# Arduino.net
KiCad netlist of a schematic drawn in Altium Designer
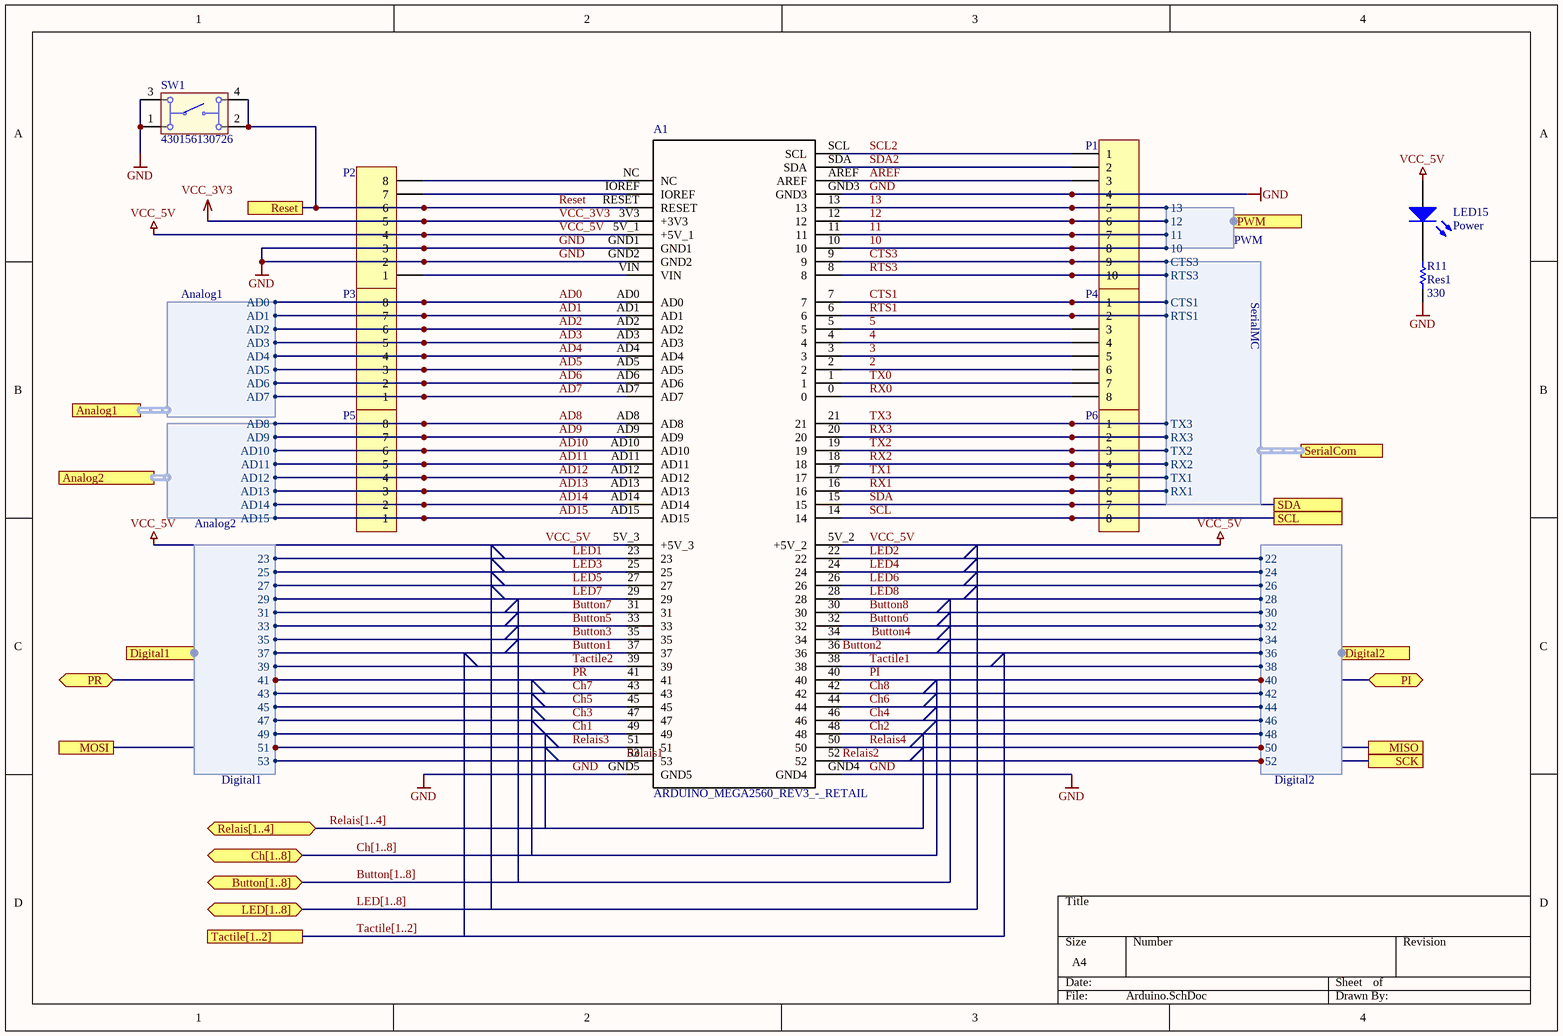
[diagram p0: Arduino.SchDoc]

(export (version "E")
  (design (tool "Eeschema 10.0.6"))
  (components
    (comp (ref "A1")
      (value "ARDUINO_MEGA2560_REV3_-_RETAIL")
      (footprint "*ARDUINO_MEGA2560_REV3_-_RETAIL_ARDUINO_MEGA2560_REV3_-_RETAIL(Primary)")
      (description "Dev.kit: Arduino; SPI, TWI, UART; ICSP, USB B, pin strips, supply")
      (fields (field (name "MF") "Arduino") (field (name "MP") "ARDUINO MEGA2560 REV3 - RETAIL"))
      (libsource (lib "ARDUINO_MEGA2560_REV3_-_RETAIL") (part "ARDUINO_MEGA2560_REV3_-_RETAIL"))
    )
    (comp (ref "LED15")
      (value "Power")
      (footprint "Type 5mm")
      (description "THT LED round mono-color waterclear, WL-TMRW, Green")
      (fields (field (name "PARTNUMBER") "151053GS03000") (field (name "MANUFACTURER") "Wuerth Elektronik"))
      (libsource (lib "Altium Content Vault") (part "WE-LED_K1A2-2"))
    )
    (comp (ref "P1")
      (value "Header 10")
      (footprint "HDR1X10")
      (description "Header, 10-Pin")
      (fields (field (name "PUBLISHER") "Altium Limited"))
      (libsource (lib "Miscellaneous Connectors") (part "Header 10"))
    )
    (comp (ref "P2")
      (value "Header 8")
      (footprint "HDR1X8")
      (description "Header, 8-Pin")
      (fields (field (name "PUBLISHER") "Altium Limited"))
      (libsource (lib "") (part "Header 8_1"))
    )
    (comp (ref "P3")
      (value "Header 8")
      (footprint "HDR1X8")
      (description "Header, 8-Pin")
      (fields (field (name "PUBLISHER") "Altium Limited"))
      (libsource (lib "") (part "Header 8_1"))
    )
    (comp (ref "P4")
      (value "Header 8")
      (footprint "HDR1X8")
      (description "Header, 8-Pin")
      (fields (field (name "PUBLISHER") "Altium Limited"))
      (libsource (lib "Miscellaneous Connectors") (part "Header 8"))
    )
    (comp (ref "P5")
      (value "Header 8")
      (footprint "HDR1X8")
      (description "Header, 8-Pin")
      (fields (field (name "PUBLISHER") "Altium Limited"))
      (libsource (lib "") (part "Header 8_1"))
    )
    (comp (ref "P6")
      (value "Header 8")
      (footprint "HDR1X8")
      (description "Header, 8-Pin")
      (fields (field (name "PUBLISHER") "Altium Limited"))
      (libsource (lib "Miscellaneous Connectors") (part "Header 8"))
    )
    (comp (ref "R11")
      (value "Res1")
      (footprint "AXIAL-0.3")
      (description "Resistor")
      (fields (field (name "ALTIUM_VALUE") "330") (field (name "PUBLISHER") "Altium Limited"))
      (libsource (lib "Miscellaneous Devices") (part "Res1"))
    )
    (comp (ref "SW1")
      (value "430156130726")
      (footprint "430156130726")
      (description "WS-TATV THT Tact Switch 6X6 mm")
      (fields (field (name "MANUFACTURER") "Wuerth Elektronik"))
      (libsource (lib "Altium Content Vault") (part "WE-TACT-SW-4"))
    )
  )
  (nets
    (net (code "7") (name "/2") (class "Default")
      (node (ref "A1") (pin "2") (pinfunction "2_2") (pintype "passive"))
      (node (ref "P4") (pin "6") (pinfunction "6_6") (pintype "passive"))
    )
    (net (code "8") (name "/3") (class "Default")
      (node (ref "A1") (pin "3") (pinfunction "3_3") (pintype "passive"))
      (node (ref "P4") (pin "5") (pinfunction "5_5") (pintype "passive"))
    )
    (net (code "9") (name "/4") (class "Default")
      (node (ref "A1") (pin "4") (pinfunction "4_4") (pintype "passive"))
      (node (ref "P4") (pin "4") (pinfunction "4_4") (pintype "passive"))
    )
    (net (code "10") (name "/5") (class "Default")
      (node (ref "A1") (pin "5") (pinfunction "5_5") (pintype "passive"))
      (node (ref "P4") (pin "3") (pinfunction "3_3") (pintype "passive"))
    )
    (net (code "11") (name "/10") (class "Default")
      (node (ref "A1") (pin "10") (pinfunction "10_10") (pintype "passive"))
      (node (ref "P1") (pin "8") (pinfunction "8_8") (pintype "passive"))
    )
    (net (code "12") (name "/11") (class "Default")
      (node (ref "A1") (pin "11") (pinfunction "11_11") (pintype "passive"))
      (node (ref "P1") (pin "7") (pinfunction "7_7") (pintype "passive"))
    )
    (net (code "13") (name "/12") (class "Default")
      (node (ref "A1") (pin "12") (pinfunction "12_12") (pintype "passive"))
      (node (ref "P1") (pin "6") (pinfunction "6_6") (pintype "passive"))
    )
    (net (code "14") (name "/13") (class "Default")
      (node (ref "A1") (pin "13") (pinfunction "13_13") (pintype "passive"))
      (node (ref "P1") (pin "5") (pinfunction "5_5") (pintype "passive"))
    )
    (net (code "15") (name "/AD0") (class "Default")
      (node (ref "A1") (pin "AD0") (pinfunction "AD0_AD0") (pintype "passive"))
      (node (ref "P3") (pin "8") (pinfunction "8_8") (pintype "passive"))
    )
    (net (code "16") (name "/AD1") (class "Default")
      (node (ref "A1") (pin "AD1") (pinfunction "AD1_AD1") (pintype "passive"))
      (node (ref "P3") (pin "7") (pinfunction "7_7") (pintype "passive"))
    )
    (net (code "17") (name "/AD2") (class "Default")
      (node (ref "A1") (pin "AD2") (pinfunction "AD2_AD2") (pintype "passive"))
      (node (ref "P3") (pin "6") (pinfunction "6_6") (pintype "passive"))
    )
    (net (code "18") (name "/AD3") (class "Default")
      (node (ref "A1") (pin "AD3") (pinfunction "AD3_AD3") (pintype "passive"))
      (node (ref "P3") (pin "5") (pinfunction "5_5") (pintype "passive"))
    )
    (net (code "19") (name "/AD4") (class "Default")
      (node (ref "A1") (pin "AD4") (pinfunction "AD4_AD4") (pintype "passive"))
      (node (ref "P3") (pin "4") (pinfunction "4_4") (pintype "passive"))
    )
    (net (code "20") (name "/AD5") (class "Default")
      (node (ref "A1") (pin "AD5") (pinfunction "AD5_AD5") (pintype "passive"))
      (node (ref "P3") (pin "3") (pinfunction "3_3") (pintype "passive"))
    )
    (net (code "21") (name "/AD6") (class "Default")
      (node (ref "A1") (pin "AD6") (pinfunction "AD6_AD6") (pintype "passive"))
      (node (ref "P3") (pin "2") (pinfunction "2_2") (pintype "passive"))
    )
    (net (code "22") (name "/AD7") (class "Default")
      (node (ref "A1") (pin "AD7") (pinfunction "AD7_AD7") (pintype "passive"))
      (node (ref "P3") (pin "1") (pinfunction "1_1") (pintype "passive"))
    )
    (net (code "23") (name "/AD8") (class "Default")
      (node (ref "A1") (pin "AD8") (pinfunction "AD8_AD8") (pintype "passive"))
      (node (ref "P5") (pin "8") (pinfunction "8_8") (pintype "passive"))
    )
    (net (code "24") (name "/AD9") (class "Default")
      (node (ref "A1") (pin "AD9") (pinfunction "AD9_AD9") (pintype "passive"))
      (node (ref "P5") (pin "7") (pinfunction "7_7") (pintype "passive"))
    )
    (net (code "25") (name "/AD10") (class "Default")
      (node (ref "A1") (pin "AD10") (pinfunction "AD10_AD10") (pintype "passive"))
      (node (ref "P5") (pin "6") (pinfunction "6_6") (pintype "passive"))
    )
    (net (code "26") (name "/AD11") (class "Default")
      (node (ref "A1") (pin "AD11") (pinfunction "AD11_AD11") (pintype "passive"))
      (node (ref "P5") (pin "5") (pinfunction "5_5") (pintype "passive"))
    )
    (net (code "27") (name "/AD12") (class "Default")
      (node (ref "A1") (pin "AD12") (pinfunction "AD12_AD12") (pintype "passive"))
      (node (ref "P5") (pin "4") (pinfunction "4_4") (pintype "passive"))
    )
    (net (code "28") (name "/AD13") (class "Default")
      (node (ref "A1") (pin "AD13") (pinfunction "AD13_AD13") (pintype "passive"))
      (node (ref "P5") (pin "3") (pinfunction "3_3") (pintype "passive"))
    )
    (net (code "29") (name "/AD14") (class "Default")
      (node (ref "A1") (pin "AD14") (pinfunction "AD14_AD14") (pintype "passive"))
      (node (ref "P5") (pin "2") (pinfunction "2_2") (pintype "passive"))
    )
    (net (code "30") (name "/AD15") (class "Default")
      (node (ref "A1") (pin "AD15") (pinfunction "AD15_AD15") (pintype "passive"))
      (node (ref "P5") (pin "1") (pinfunction "1_1") (pintype "passive"))
    )
    (net (code "31") (name "/AREF") (class "Default")
      (node (ref "A1") (pin "AREF") (pinfunction "AREF_AREF") (pintype "passive"))
      (node (ref "P1") (pin "3") (pinfunction "3_3") (pintype "passive"))
    )
    (net (code "32") (name "/Button1") (class "Default")
      (node (ref "A1") (pin "37") (pinfunction "37_37") (pintype "passive"))
    )
    (net (code "33") (name "/Button2") (class "Default")
      (node (ref "A1") (pin "36") (pinfunction "36_36") (pintype "passive"))
    )
    (net (code "34") (name "/Button3") (class "Default")
      (node (ref "A1") (pin "35") (pinfunction "35_35") (pintype "passive"))
    )
    (net (code "35") (name "/Button4") (class "Default")
      (node (ref "A1") (pin "34") (pinfunction "34_34") (pintype "passive"))
    )
    (net (code "36") (name "/Button5") (class "Default")
      (node (ref "A1") (pin "33") (pinfunction "33_33") (pintype "passive"))
    )
    (net (code "37") (name "/Button6") (class "Default")
      (node (ref "A1") (pin "32") (pinfunction "32_32") (pintype "passive"))
    )
    (net (code "38") (name "/Button7") (class "Default")
      (node (ref "A1") (pin "31") (pinfunction "31_31") (pintype "passive"))
    )
    (net (code "39") (name "/Button8") (class "Default")
      (node (ref "A1") (pin "30") (pinfunction "30_30") (pintype "passive"))
    )
    (net (code "41") (name "/CTS1") (class "Default")
      (node (ref "A1") (pin "7") (pinfunction "7_7") (pintype "passive"))
      (node (ref "P4") (pin "1") (pinfunction "1_1") (pintype "passive"))
    )
    (net (code "42") (name "/CTS3") (class "Default")
      (node (ref "A1") (pin "9") (pinfunction "9_9") (pintype "passive"))
      (node (ref "P1") (pin "9") (pinfunction "9_9") (pintype "passive"))
    )
    (net (code "43") (name "/Ch1") (class "Default")
      (node (ref "A1") (pin "49") (pinfunction "49_49") (pintype "passive"))
    )
    (net (code "44") (name "/Ch2") (class "Default")
      (node (ref "A1") (pin "48") (pinfunction "48_48") (pintype "passive"))
    )
    (net (code "45") (name "/Ch3") (class "Default")
      (node (ref "A1") (pin "47") (pinfunction "47_47") (pintype "passive"))
    )
    (net (code "46") (name "/Ch4") (class "Default")
      (node (ref "A1") (pin "46") (pinfunction "46_46") (pintype "passive"))
    )
    (net (code "47") (name "/Ch5") (class "Default")
      (node (ref "A1") (pin "45") (pinfunction "45_45") (pintype "passive"))
    )
    (net (code "48") (name "/Ch6") (class "Default")
      (node (ref "A1") (pin "44") (pinfunction "44_44") (pintype "passive"))
    )
    (net (code "49") (name "/Ch7") (class "Default")
      (node (ref "A1") (pin "43") (pinfunction "43_43") (pintype "passive"))
    )
    (net (code "50") (name "/Ch8") (class "Default")
      (node (ref "A1") (pin "42") (pinfunction "42_42") (pintype "passive"))
    )
    (net (code "52") (name "/LED1") (class "Default")
      (node (ref "A1") (pin "23") (pinfunction "23_23") (pintype "passive"))
    )
    (net (code "53") (name "/LED2") (class "Default")
      (node (ref "A1") (pin "22") (pinfunction "22_22") (pintype "passive"))
    )
    (net (code "54") (name "/LED3") (class "Default")
      (node (ref "A1") (pin "25") (pinfunction "25_25") (pintype "passive"))
    )
    (net (code "55") (name "/LED4") (class "Default")
      (node (ref "A1") (pin "24") (pinfunction "24_24") (pintype "passive"))
    )
    (net (code "56") (name "/LED5") (class "Default")
      (node (ref "A1") (pin "27") (pinfunction "27_27") (pintype "passive"))
    )
    (net (code "57") (name "/LED6") (class "Default")
      (node (ref "A1") (pin "26") (pinfunction "26_26") (pintype "passive"))
    )
    (net (code "58") (name "/LED7") (class "Default")
      (node (ref "A1") (pin "29") (pinfunction "29_29") (pintype "passive"))
    )
    (net (code "59") (name "/LED8") (class "Default")
      (node (ref "A1") (pin "28") (pinfunction "28_28") (pintype "passive"))
    )
    (net (code "61") (name "/PI") (class "Default")
      (node (ref "A1") (pin "40") (pinfunction "40_40") (pintype "passive"))
    )
    (net (code "62") (name "/PR") (class "Default")
      (node (ref "A1") (pin "41") (pinfunction "41_41") (pintype "passive"))
    )
    (net (code "63") (name "/RTS1") (class "Default")
      (node (ref "A1") (pin "6") (pinfunction "6_6") (pintype "passive"))
      (node (ref "P4") (pin "2") (pinfunction "2_2") (pintype "passive"))
    )
    (net (code "64") (name "/RTS3") (class "Default")
      (node (ref "A1") (pin "8") (pinfunction "8_8") (pintype "passive"))
      (node (ref "P1") (pin "10") (pinfunction "10_10") (pintype "passive"))
    )
    (net (code "65") (name "/RX0") (class "Default")
      (node (ref "A1") (pin "0") (pinfunction "0_0") (pintype "passive"))
      (node (ref "P4") (pin "8") (pinfunction "8_8") (pintype "passive"))
    )
    (net (code "66") (name "/RX1") (class "Default")
      (node (ref "A1") (pin "16") (pinfunction "16_16") (pintype "passive"))
      (node (ref "P6") (pin "6") (pinfunction "6_6") (pintype "passive"))
    )
    (net (code "67") (name "/RX2") (class "Default")
      (node (ref "A1") (pin "18") (pinfunction "18_18") (pintype "passive"))
      (node (ref "P6") (pin "4") (pinfunction "4_4") (pintype "passive"))
    )
    (net (code "68") (name "/RX3") (class "Default")
      (node (ref "A1") (pin "20") (pinfunction "20_20") (pintype "passive"))
      (node (ref "P6") (pin "2") (pinfunction "2_2") (pintype "passive"))
    )
    (net (code "69") (name "/Relais1") (class "Default")
      (node (ref "A1") (pin "53") (pinfunction "53_53") (pintype "passive"))
    )
    (net (code "70") (name "/Relais2") (class "Default")
      (node (ref "A1") (pin "52") (pinfunction "52_52") (pintype "passive"))
    )
    (net (code "71") (name "/Relais3") (class "Default")
      (node (ref "A1") (pin "51") (pinfunction "51_51") (pintype "passive"))
    )
    (net (code "72") (name "/Relais4") (class "Default")
      (node (ref "A1") (pin "50") (pinfunction "50_50") (pintype "passive"))
    )
    (net (code "74") (name "/Reset") (class "Default")
      (node (ref "A1") (pin "RESET") (pinfunction "RESET_RESET") (pintype "passive"))
      (node (ref "P2") (pin "6") (pinfunction "6_6") (pintype "passive"))
      (node (ref "SW1") (pin "2") (pinfunction "2_2") (pintype "passive"))
      (node (ref "SW1") (pin "4") (pinfunction "4_4") (pintype "passive"))
    )
    (net (code "75") (name "/SCL") (class "Default")
      (node (ref "A1") (pin "14") (pinfunction "14_14") (pintype "passive"))
      (node (ref "P6") (pin "8") (pinfunction "8_8") (pintype "passive"))
    )
    (net (code "76") (name "/SCL2") (class "Default")
      (node (ref "A1") (pin "SCL") (pinfunction "SCL_SCL") (pintype "passive"))
      (node (ref "P1") (pin "1") (pinfunction "1_1") (pintype "passive"))
    )
    (net (code "77") (name "/SDA") (class "Default")
      (node (ref "A1") (pin "15") (pinfunction "15_15") (pintype "passive"))
      (node (ref "P6") (pin "7") (pinfunction "7_7") (pintype "passive"))
    )
    (net (code "78") (name "/SDA2") (class "Default")
      (node (ref "A1") (pin "SDA") (pinfunction "SDA_SDA") (pintype "passive"))
      (node (ref "P1") (pin "2") (pinfunction "2_2") (pintype "passive"))
    )
    (net (code "79") (name "/TX0") (class "Default")
      (node (ref "A1") (pin "1") (pinfunction "1_1") (pintype "passive"))
      (node (ref "P4") (pin "7") (pinfunction "7_7") (pintype "passive"))
    )
    (net (code "80") (name "/TX1") (class "Default")
      (node (ref "A1") (pin "17") (pinfunction "17_17") (pintype "passive"))
      (node (ref "P6") (pin "5") (pinfunction "5_5") (pintype "passive"))
    )
    (net (code "81") (name "/TX2") (class "Default")
      (node (ref "A1") (pin "19") (pinfunction "19_19") (pintype "passive"))
      (node (ref "P6") (pin "3") (pinfunction "3_3") (pintype "passive"))
    )
    (net (code "82") (name "/TX3") (class "Default")
      (node (ref "A1") (pin "21") (pinfunction "21_21") (pintype "passive"))
      (node (ref "P6") (pin "1") (pinfunction "1_1") (pintype "passive"))
    )
    (net (code "83") (name "/Tactile1") (class "Default")
      (node (ref "A1") (pin "38") (pinfunction "38_38") (pintype "passive"))
    )
    (net (code "84") (name "/Tactile2") (class "Default")
      (node (ref "A1") (pin "39") (pinfunction "39_39") (pintype "passive"))
    )
    (net (code "92") (name "GND") (class "Default")
      (node (ref "A1") (pin "GND1") (pinfunction "GND1_GND1") (pintype "passive"))
      (node (ref "A1") (pin "GND2") (pinfunction "GND2_GND2") (pintype "passive"))
      (node (ref "A1") (pin "GND3") (pinfunction "GND3_GND3") (pintype "passive"))
      (node (ref "A1") (pin "GND4") (pinfunction "GND4_GND4") (pintype "passive"))
      (node (ref "A1") (pin "GND5") (pinfunction "GND5_GND5") (pintype "passive"))
      (node (ref "P1") (pin "4") (pinfunction "4_4") (pintype "passive"))
      (node (ref "P2") (pin "2") (pinfunction "2_2") (pintype "passive"))
      (node (ref "P2") (pin "3") (pinfunction "3_3") (pintype "passive"))
      (node (ref "R11") (pin "1") (pinfunction "1_1") (pintype "passive"))
      (node (ref "SW1") (pin "1") (pinfunction "1_1") (pintype "passive"))
      (node (ref "SW1") (pin "3") (pinfunction "3_3") (pintype "passive"))
    )
    (net (code "93") (name "Net-(A1-PadIOREF)") (class "Default")
      (node (ref "A1") (pin "IOREF") (pinfunction "IOREF_IOREF") (pintype "passive"))
      (node (ref "P2") (pin "7") (pinfunction "7_7") (pintype "passive"))
    )
    (net (code "94") (name "Net-(A1-PadNC)") (class "Default")
      (node (ref "A1") (pin "NC") (pinfunction "NC_NC") (pintype "passive"))
      (node (ref "P2") (pin "8") (pinfunction "8_8") (pintype "passive"))
    )
    (net (code "95") (name "Net-(A1-PadVIN)") (class "Default")
      (node (ref "A1") (pin "VIN") (pinfunction "VIN_VIN") (pintype "passive"))
      (node (ref "P2") (pin "1") (pinfunction "1_1") (pintype "passive"))
    )
    (net (code "96") (name "Net-(LED15-K)") (class "Default")
      (node (ref "LED15") (pin "1") (pinfunction "K_1") (pintype "passive"))
      (node (ref "R11") (pin "2") (pinfunction "2_2") (pintype "passive"))
    )
    (net (code "97") (name "VCC_3V3") (class "Default")
      (node (ref "A1") (pin "3V3") (pinfunction "+3V3_3V3") (pintype "passive"))
      (node (ref "P2") (pin "5") (pinfunction "5_5") (pintype "passive"))
    )
    (net (code "98") (name "VCC_5V") (class "Default")
      (node (ref "A1") (pin "5V_1") (pinfunction "+5V_1_5V_1") (pintype "passive"))
      (node (ref "A1") (pin "5V_2") (pinfunction "+5V_2_5V_2") (pintype "passive"))
      (node (ref "A1") (pin "5V_3") (pinfunction "+5V_3_5V_3") (pintype "passive"))
      (node (ref "LED15") (pin "2") (pinfunction "A_2") (pintype "passive"))
      (node (ref "P2") (pin "4") (pinfunction "4_4") (pintype "passive"))
    )
  )
)
